# Open433_2020-06-20_13-22-58.net
KiCad netlist of a schematic drawn in EasyEDA
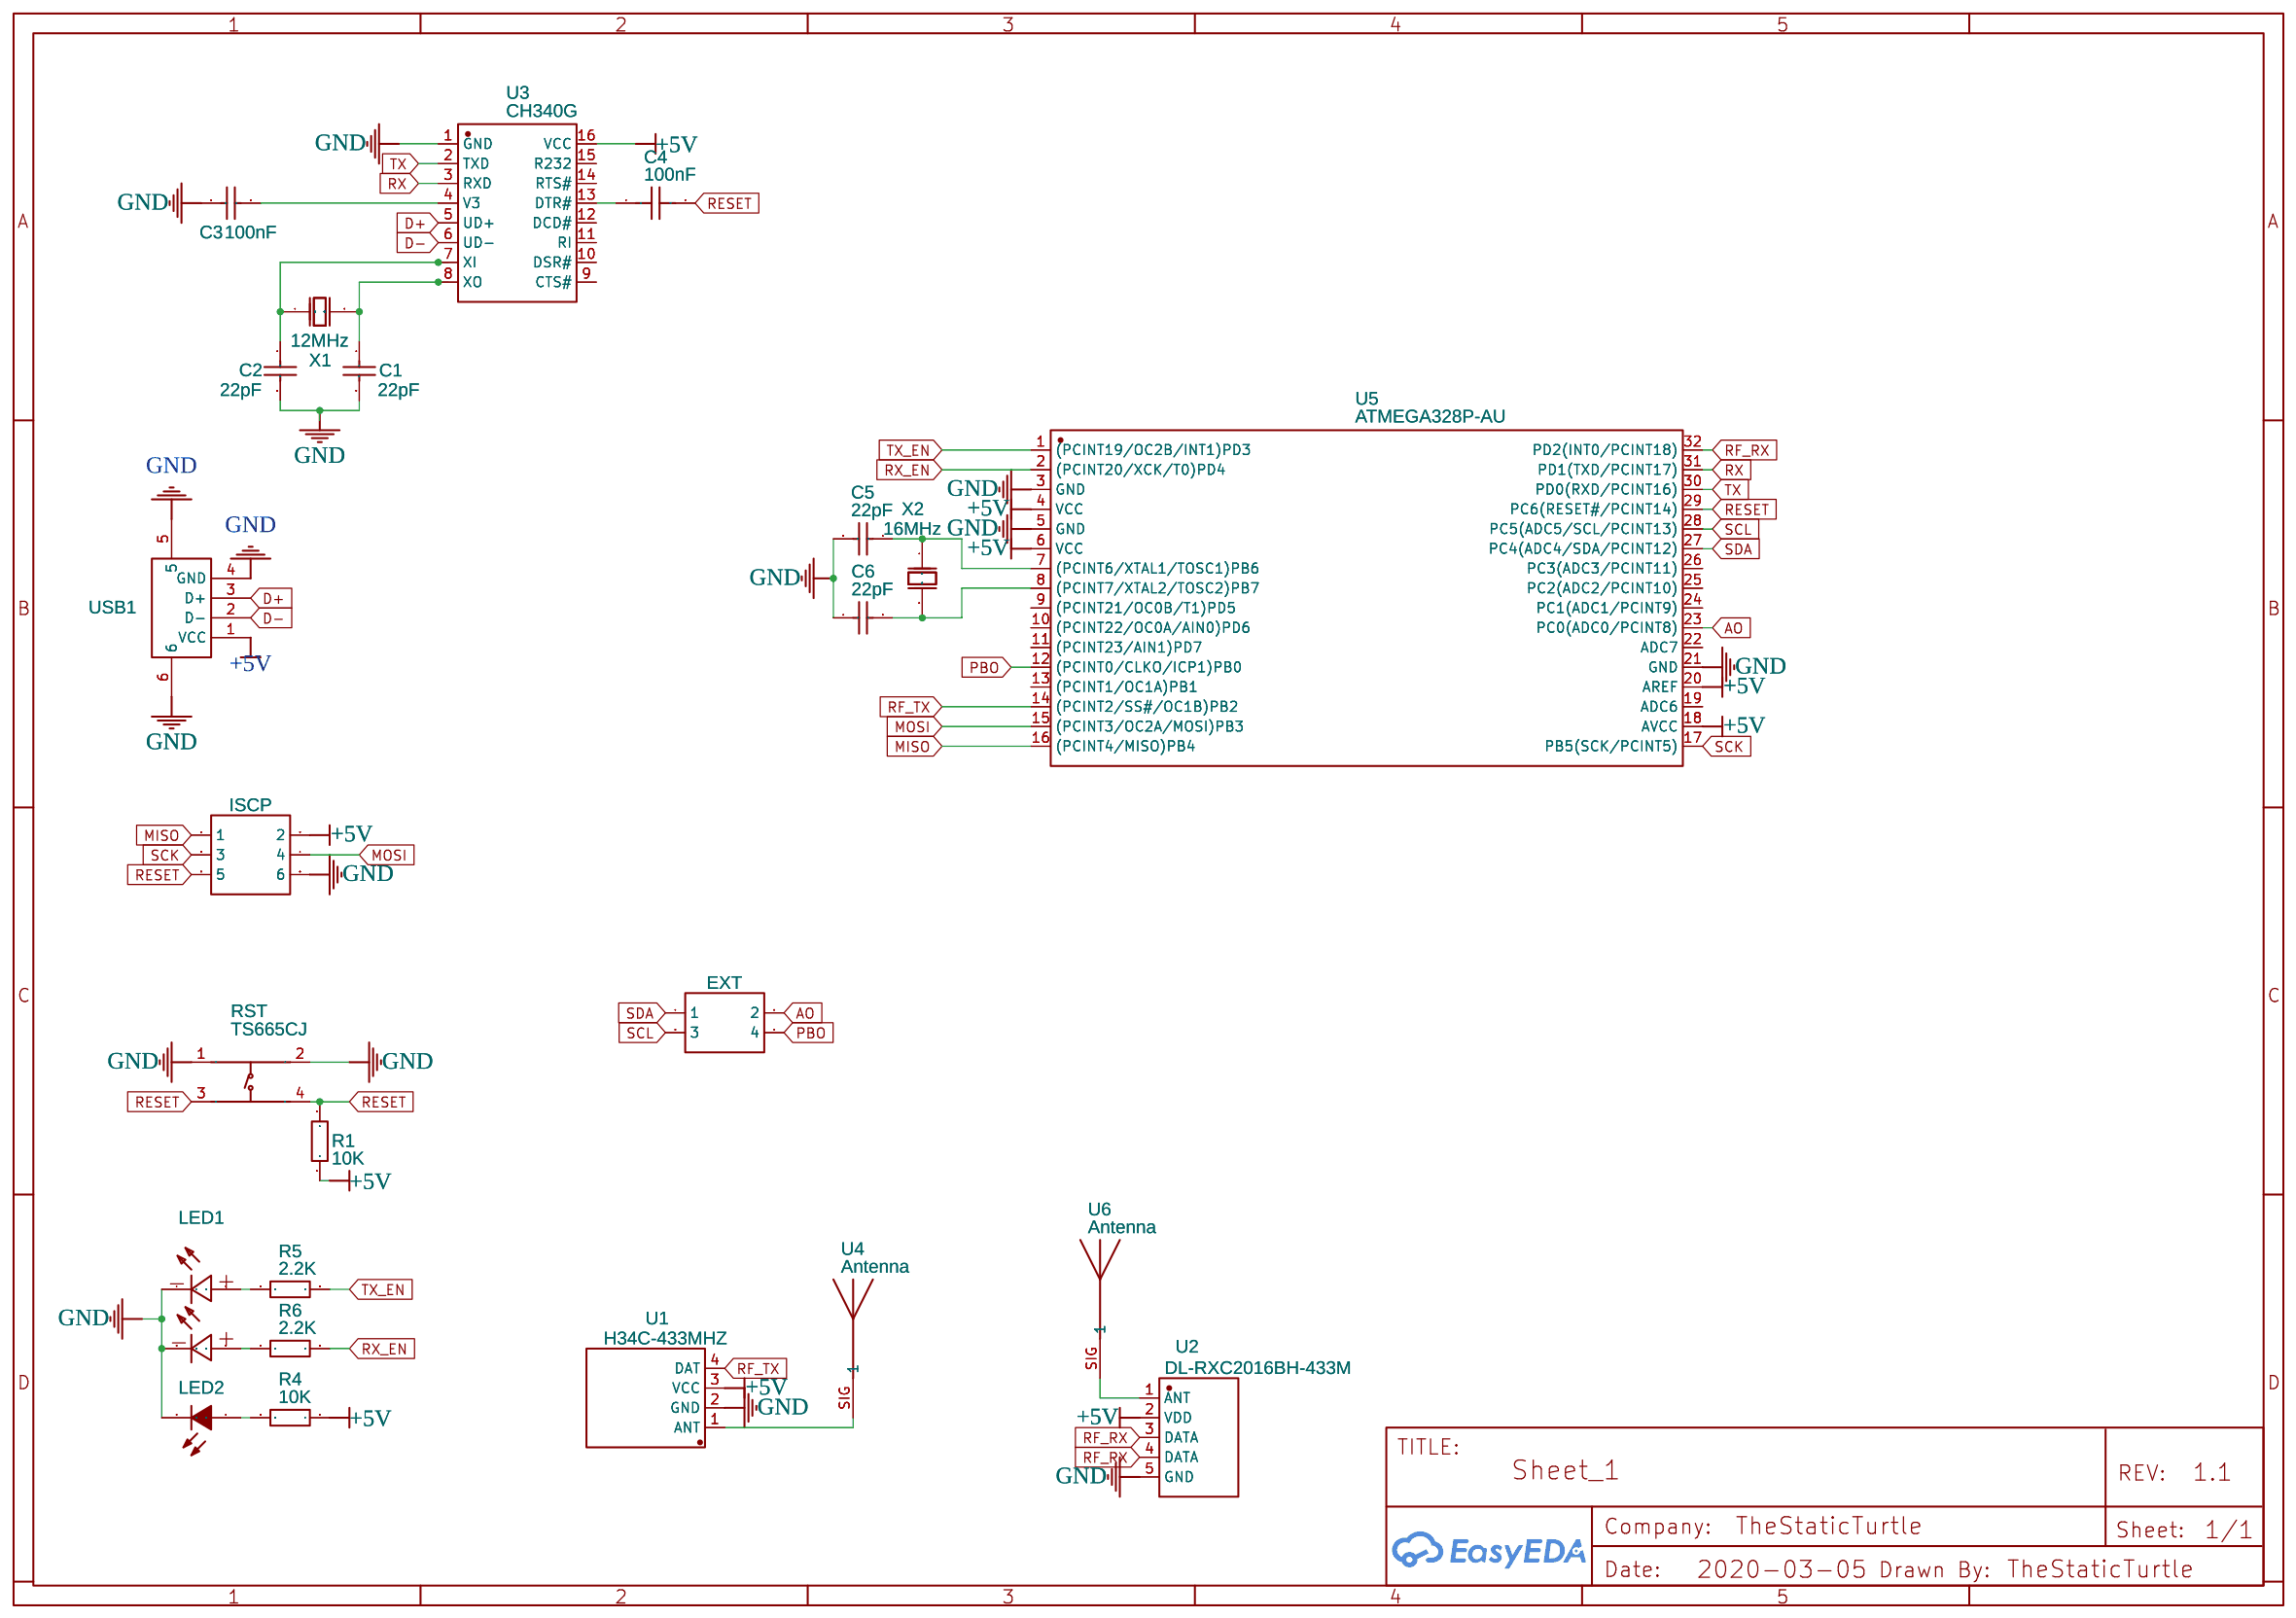
[diagram p0: schematic sheet]

(export (version "E")
  (design (tool "Eeschema 10.0.6"))
  (components
    (comp (ref "C1")
      (value "22pF")
      (fields
        (field (name "BOM_Manufacturer Part") "1206CG220J500NT")
        (field (name "BOM_Supplier Part") "C1896")
      )
      (libsource (lib "") (part "1206CG220J500NT_1"))
    )
    (comp (ref "C2")
      (value "22pF")
      (fields
        (field (name "BOM_Manufacturer Part") "1206CG220J500NT")
        (field (name "BOM_Supplier Part") "C1896")
      )
      (libsource (lib "") (part "1206CG220J500NT_1"))
    )
    (comp (ref "C3")
      (value "100nF")
      (fields
        (field (name "BOM_Manufacturer Part") "GRM31C5C1H104JA01L")
        (field (name "BOM_Supplier Part") "C97946")
      )
      (libsource (lib "") (part "GRM31C5C1H104JA01L"))
    )
    (comp (ref "C4")
      (value "100nF")
      (fields
        (field (name "BOM_Manufacturer Part") "FM31X104K251EEG")
        (field (name "BOM_Supplier Part") "C365814")
      )
      (libsource (lib "") (part "FM31X104K251EEG"))
    )
    (comp (ref "C5")
      (value "22pF")
      (fields
        (field (name "BOM_Manufacturer Part") "1206CG220J500NT")
        (field (name "BOM_Supplier Part") "C1896")
      )
      (libsource (lib "") (part "1206CG220J500NT"))
    )
    (comp (ref "C6")
      (value "22pF")
      (fields
        (field (name "BOM_Manufacturer Part") "1206CG220J500NT")
        (field (name "BOM_Supplier Part") "C1896")
      )
      (libsource (lib "") (part "1206CG220J500NT_2"))
    )
    (comp (ref "EXT")
      (value "HDR-M-2.54_2x2")
      (fields (field (name "BOM_Supplier Part") "C66690"))
      (libsource (lib "") (part "HDR-M-2.54_2x2"))
    )
    (comp (ref "ISCP")
      (value "Header-Female-2.54_2x3")
      (fields
        (field (name "BOM_Manufacturer Part") "DS1023-2*3SF11")
        (field (name "BOM_Supplier Part") "C92272")
      )
      (libsource (lib "") (part "Header-Female-2.54_2x3"))
    )
    (comp (ref "LED1")
      (value "19-223/Y2R6C-A01/2T")
      (fields (field (name "BOM_Supplier Part") "C282134"))
      (libsource (lib "") (part "19-223/Y2R6C-A01/2T"))
    )
    (comp (ref "LED2")
      (value "19-217/GHC-YR1S2/3T")
      (fields (field (name "BOM_Supplier Part") "C72043"))
      (libsource (lib "") (part "19-217/GHC-YR1S2/3T"))
    )
    (comp (ref "R1")
      (value "10K")
      (fields
        (field (name "BOM_Manufacturer Part") "CR-06JL7---10K")
        (field (name "BOM_Supplier Part") "C280032")
      )
      (libsource (lib "") (part "CR-06JL7---10K"))
    )
    (comp (ref "R4")
      (value "10K")
      (fields
        (field (name "BOM_Manufacturer Part") "CR-06JL7---10K")
        (field (name "BOM_Supplier Part") "C280032")
      )
      (libsource (lib "") (part "CR-06JL7---10K_1"))
    )
    (comp (ref "R5")
      (value "2.2K")
      (fields
        (field (name "BOM_Manufacturer Part") "QR0603F2K2P05")
        (field (name "BOM_Supplier Part") "C176136")
      )
      (libsource (lib "") (part "QR0603F2K2P05"))
    )
    (comp (ref "R6")
      (value "2.2K")
      (fields
        (field (name "BOM_Manufacturer Part") "QR0603F2K2P05")
        (field (name "BOM_Supplier Part") "C176136")
      )
      (libsource (lib "") (part "QR0603F2K2P05"))
    )
    (comp (ref "RST")
      (value "TS665CJ")
      (fields (field (name "BOM_Supplier Part") "C393938"))
      (libsource (lib "") (part "TS665CJ"))
    )
    (comp (ref "U1")
      (value "H34C-433MHZ")
      (fields (field (name "BOM_Supplier Part") "C131030"))
      (libsource (lib "") (part "H34C-433MHZ"))
    )
    (comp (ref "U2")
      (value "DL-RXC2016BH-433M")
      (fields (field (name "BOM_Supplier Part") "C381154"))
      (libsource (lib "") (part "DL-RXC2016BH-433M"))
    )
    (comp (ref "U3")
      (value "CH340G")
      (fields (field (name "BOM_Supplier Part") "C14267"))
      (libsource (lib "") (part "CH340G"))
    )
    (comp (ref "U4")
      (value "Antenna")
      (fields (field (name "BOM_Manufacturer Part") "ANT"))
      (libsource (lib "") (part "Antenna"))
    )
    (comp (ref "U5")
      (value "ATMEGA328P-AU")
      (fields (field (name "BOM_Supplier Part") "C14877"))
      (libsource (lib "") (part "ATMEGA328P-AU"))
    )
    (comp (ref "U6")
      (value "Antenna")
      (fields (field (name "BOM_Manufacturer Part") "ANT"))
      (libsource (lib "") (part "Antenna"))
    )
    (comp (ref "USB1")
      (value "U217-04XN-XXR84")
      (fields (field (name "BOM_Supplier Part") "C319178"))
      (libsource (lib "") (part "U217-04XN-XXR84"))
    )
    (comp (ref "X1")
      (value "12MHz")
      (fields
        (field (name "BOM_Manufacturer Part") "C12000J517")
        (field (name "BOM_Supplier Part") "C279578")
      )
      (libsource (lib "") (part "C12000J517"))
    )
    (comp (ref "X2")
      (value "16MHz")
      (fields
        (field (name "BOM_Manufacturer Part") "49MD-16.000-20-20-20/A")
        (field (name "BOM_Supplier Part") "C240963")
      )
      (libsource (lib "") (part "49MD-16.000-20-20-20/A"))
    )
  )
  (nets
    (net (code "1") (name "+5V") (class "Default")
      (node (ref "ISCP") (pin "2") (pinfunction "2_2") (pintype "input"))
      (node (ref "R1") (pin "1") (pinfunction "1_1") (pintype "unspecified"))
      (node (ref "R4") (pin "1") (pinfunction "1_1") (pintype "unspecified"))
      (node (ref "U1") (pin "3") (pinfunction "VCC_3") (pintype "unspecified"))
      (node (ref "U2") (pin "2") (pinfunction "VDD_2") (pintype "unspecified"))
      (node (ref "U3") (pin "16") (pinfunction "VCC_16") (pintype "unspecified"))
      (node (ref "U5") (pin "18") (pinfunction "AVCC_18") (pintype "unspecified"))
      (node (ref "U5") (pin "20") (pinfunction "AREF_20") (pintype "unspecified"))
      (node (ref "U5") (pin "4") (pinfunction "VCC_4") (pintype "unspecified"))
      (node (ref "U5") (pin "6") (pinfunction "VCC_6") (pintype "unspecified"))
      (node (ref "USB1") (pin "1") (pinfunction "VCC_1") (pintype "unspecified"))
    )
    (net (code "2") (name "AO") (class "Default")
      (node (ref "EXT") (pin "2") (pinfunction "2_2") (pintype "input"))
      (node (ref "U5") (pin "23") (pinfunction "PC0(ADC0/PCINT8)_23") (pintype "unspecified"))
    )
    (net (code "3") (name "D+") (class "Default")
      (node (ref "U3") (pin "5") (pinfunction "UD+_5") (pintype "unspecified"))
      (node (ref "USB1") (pin "3") (pinfunction "D+_3") (pintype "unspecified"))
    )
    (net (code "4") (name "D-") (class "Default")
      (node (ref "U3") (pin "6") (pinfunction "UD-_6") (pintype "unspecified"))
      (node (ref "USB1") (pin "2") (pinfunction "D-_2") (pintype "unspecified"))
    )
    (net (code "5") (name "GND") (class "Default")
      (node (ref "C1") (pin "2") (pinfunction "2_2") (pintype "input"))
      (node (ref "C2") (pin "2") (pinfunction "2_2") (pintype "input"))
      (node (ref "C3") (pin "1") (pinfunction "1_1") (pintype "input"))
      (node (ref "C5") (pin "2") (pinfunction "2_2") (pintype "input"))
      (node (ref "C6") (pin "1") (pinfunction "1_1") (pintype "input"))
      (node (ref "ISCP") (pin "6") (pinfunction "6_6") (pintype "input"))
      (node (ref "LED1") (pin "3") (pinfunction "3_3") (pintype "unspecified"))
      (node (ref "LED1") (pin "4") (pinfunction "4_4") (pintype "unspecified"))
      (node (ref "LED2") (pin "2") (pinfunction "C_2") (pintype "input"))
      (node (ref "RST") (pin "1") (pinfunction "A_1") (pintype "unspecified"))
      (node (ref "RST") (pin "2") (pinfunction "B_2") (pintype "unspecified"))
      (node (ref "U1") (pin "2") (pinfunction "GND_2") (pintype "unspecified"))
      (node (ref "U2") (pin "5") (pinfunction "GND_5") (pintype "unspecified"))
      (node (ref "U3") (pin "1") (pinfunction "GND_1") (pintype "unspecified"))
      (node (ref "U5") (pin "21") (pinfunction "GND_21") (pintype "unspecified"))
      (node (ref "U5") (pin "3") (pinfunction "GND_3") (pintype "unspecified"))
      (node (ref "U5") (pin "5") (pinfunction "GND_5") (pintype "unspecified"))
      (node (ref "USB1") (pin "4") (pinfunction "GND_4") (pintype "unspecified"))
      (node (ref "USB1") (pin "5") (pinfunction "5_5") (pintype "unspecified"))
      (node (ref "USB1") (pin "6") (pinfunction "6_6") (pintype "unspecified"))
    )
    (net (code "6") (name "MISO") (class "Default")
      (node (ref "ISCP") (pin "1") (pinfunction "1_1") (pintype "input"))
      (node (ref "U5") (pin "16") (pinfunction "(PCINT4/MISO)PB4_16") (pintype "unspecified"))
    )
    (net (code "7") (name "MOSI") (class "Default")
      (node (ref "ISCP") (pin "4") (pinfunction "4_4") (pintype "input"))
      (node (ref "U5") (pin "15") (pinfunction "(PCINT3/OC2A/MOSI)PB3_15") (pintype "unspecified"))
    )
    (net (code "8") (name "Net-(LED1-Pad1)") (class "Default")
      (node (ref "LED1") (pin "1") (pinfunction "1_1") (pintype "unspecified"))
      (node (ref "R5") (pin "1") (pinfunction "1_1") (pintype "unspecified"))
    )
    (net (code "9") (name "Net-(LED1-Pad2)") (class "Default")
      (node (ref "LED1") (pin "2") (pinfunction "2_2") (pintype "unspecified"))
      (node (ref "R6") (pin "1") (pinfunction "1_1") (pintype "unspecified"))
    )
    (net (code "10") (name "Net-(LED2-A)") (class "Default")
      (node (ref "LED2") (pin "1") (pinfunction "A_1") (pintype "input"))
      (node (ref "R4") (pin "2") (pinfunction "2_2") (pintype "unspecified"))
    )
    (net (code "11") (name "Net-(U1-ANT)") (class "Default")
      (node (ref "U1") (pin "1") (pinfunction "ANT_1") (pintype "unspecified"))
      (node (ref "U4") (pin "SIG") (pinfunction "1_SIG") (pintype "unspecified"))
    )
    (net (code "12") (name "Net-(U2-ANT)") (class "Default")
      (node (ref "U2") (pin "1") (pinfunction "ANT_1") (pintype "unspecified"))
      (node (ref "U6") (pin "SIG") (pinfunction "1_SIG") (pintype "unspecified"))
    )
    (net (code "13") (name "Net-(U3-DTR#)") (class "Default")
      (node (ref "C4") (pin "1") (pinfunction "1_1") (pintype "unspecified"))
      (node (ref "U3") (pin "13") (pinfunction "DTR#_13") (pintype "unspecified"))
    )
    (net (code "14") (name "Net-(U3-V3)") (class "Default")
      (node (ref "C3") (pin "2") (pinfunction "2_2") (pintype "input"))
      (node (ref "U3") (pin "4") (pinfunction "V3_4") (pintype "unspecified"))
    )
    (net (code "15") (name "Net-(U3-XI)") (class "Default")
      (node (ref "C2") (pin "1") (pinfunction "1_1") (pintype "input"))
      (node (ref "U3") (pin "7") (pinfunction "XI_7") (pintype "unspecified"))
      (node (ref "X1") (pin "1") (pinfunction "OSC1_1") (pintype "input"))
    )
    (net (code "16") (name "Net-(U3-XO)") (class "Default")
      (node (ref "C1") (pin "1") (pinfunction "1_1") (pintype "input"))
      (node (ref "U3") (pin "8") (pinfunction "XO_8") (pintype "unspecified"))
      (node (ref "X1") (pin "2") (pinfunction "OSC2_2") (pintype "input"))
    )
    (net (code "17") (name "Net-(U5-(PCINT6{slash}XTAL1{slash}TOSC1)PB6)") (class "Default")
      (node (ref "C5") (pin "1") (pinfunction "1_1") (pintype "input"))
      (node (ref "U5") (pin "7") (pinfunction "(PCINT6/XTAL1/TOSC1)PB6_7") (pintype "unspecified"))
      (node (ref "X2") (pin "1") (pinfunction "OSC1_1") (pintype "input"))
    )
    (net (code "18") (name "Net-(U5-(PCINT7{slash}XTAL2{slash}TOSC2)PB7)") (class "Default")
      (node (ref "C6") (pin "2") (pinfunction "2_2") (pintype "input"))
      (node (ref "U5") (pin "8") (pinfunction "(PCINT7/XTAL2/TOSC2)PB7_8") (pintype "unspecified"))
      (node (ref "X2") (pin "2") (pinfunction "OSC2_2") (pintype "input"))
    )
    (net (code "19") (name "PBO") (class "Default")
      (node (ref "EXT") (pin "4") (pinfunction "4_4") (pintype "input"))
      (node (ref "U5") (pin "12") (pinfunction "(PCINT0/CLKO/ICP1)PB0_12") (pintype "unspecified"))
    )
    (net (code "20") (name "RESET") (class "Default")
      (node (ref "C4") (pin "2") (pinfunction "2_2") (pintype "unspecified"))
      (node (ref "ISCP") (pin "5") (pinfunction "5_5") (pintype "input"))
      (node (ref "R1") (pin "2") (pinfunction "2_2") (pintype "unspecified"))
      (node (ref "RST") (pin "3") (pinfunction "C_3") (pintype "unspecified"))
      (node (ref "RST") (pin "4") (pinfunction "D_4") (pintype "unspecified"))
      (node (ref "U5") (pin "29") (pinfunction "PC6(RESET#/PCINT14)_29") (pintype "unspecified"))
    )
    (net (code "21") (name "RF_RX") (class "Default")
      (node (ref "U2") (pin "3") (pinfunction "DATA_3") (pintype "unspecified"))
      (node (ref "U2") (pin "4") (pinfunction "DATA_4") (pintype "unspecified"))
      (node (ref "U5") (pin "32") (pinfunction "PD2(INT0/PCINT18)_32") (pintype "unspecified"))
    )
    (net (code "22") (name "RF_TX") (class "Default")
      (node (ref "U1") (pin "4") (pinfunction "DAT_4") (pintype "unspecified"))
      (node (ref "U5") (pin "14") (pinfunction "(PCINT2/SS#/OC1B)PB2_14") (pintype "unspecified"))
    )
    (net (code "23") (name "RX") (class "Default")
      (node (ref "U3") (pin "3") (pinfunction "RXD_3") (pintype "unspecified"))
      (node (ref "U5") (pin "31") (pinfunction "PD1(TXD/PCINT17)_31") (pintype "unspecified"))
    )
    (net (code "24") (name "RX_EN") (class "Default")
      (node (ref "R6") (pin "2") (pinfunction "2_2") (pintype "unspecified"))
      (node (ref "U5") (pin "2") (pinfunction "(PCINT20/XCK/T0)PD4_2") (pintype "unspecified"))
    )
    (net (code "25") (name "SCK") (class "Default")
      (node (ref "ISCP") (pin "3") (pinfunction "3_3") (pintype "input"))
      (node (ref "U5") (pin "17") (pinfunction "PB5(SCK/PCINT5)_17") (pintype "unspecified"))
    )
    (net (code "26") (name "SCL") (class "Default")
      (node (ref "EXT") (pin "3") (pinfunction "3_3") (pintype "input"))
      (node (ref "U5") (pin "28") (pinfunction "PC5(ADC5/SCL/PCINT13)_28") (pintype "unspecified"))
    )
    (net (code "27") (name "SDA") (class "Default")
      (node (ref "EXT") (pin "1") (pinfunction "1_1") (pintype "input"))
      (node (ref "U5") (pin "27") (pinfunction "PC4(ADC4/SDA/PCINT12)_27") (pintype "unspecified"))
    )
    (net (code "28") (name "TX") (class "Default")
      (node (ref "U3") (pin "2") (pinfunction "TXD_2") (pintype "unspecified"))
      (node (ref "U5") (pin "30") (pinfunction "PD0(RXD/PCINT16)_30") (pintype "unspecified"))
    )
    (net (code "29") (name "TX_EN") (class "Default")
      (node (ref "R5") (pin "2") (pinfunction "2_2") (pintype "unspecified"))
      (node (ref "U5") (pin "1") (pinfunction "(PCINT19/OC2B/INT1)PD3_1") (pintype "unspecified"))
    )
    (net (code "30") (name "unconnected-(U3-CTS#-Pad9)") (class "Default")
      (node (ref "U3") (pin "9") (pinfunction "CTS#_9") (pintype "unspecified"))
    )
    (net (code "31") (name "unconnected-(U3-DCD#-Pad12)") (class "Default")
      (node (ref "U3") (pin "12") (pinfunction "DCD#_12") (pintype "unspecified"))
    )
    (net (code "32") (name "unconnected-(U3-DSR#-Pad10)") (class "Default")
      (node (ref "U3") (pin "10") (pinfunction "DSR#_10") (pintype "unspecified"))
    )
    (net (code "33") (name "unconnected-(U3-R232-Pad15)") (class "Default")
      (node (ref "U3") (pin "15") (pinfunction "R232_15") (pintype "unspecified"))
    )
    (net (code "34") (name "unconnected-(U3-RI-Pad11)") (class "Default")
      (node (ref "U3") (pin "11") (pinfunction "RI_11") (pintype "unspecified"))
    )
    (net (code "35") (name "unconnected-(U3-RTS#-Pad14)") (class "Default")
      (node (ref "U3") (pin "14") (pinfunction "RTS#_14") (pintype "unspecified"))
    )
    (net (code "36") (name "unconnected-(U5-(PCINT1{slash}OC1A)PB1-Pad13)") (class "Default")
      (node (ref "U5") (pin "13") (pinfunction "(PCINT1/OC1A)PB1_13") (pintype "unspecified"))
    )
    (net (code "37") (name "unconnected-(U5-(PCINT21{slash}OC0B{slash}T1)PD5-Pad9)") (class "Default")
      (node (ref "U5") (pin "9") (pinfunction "(PCINT21/OC0B/T1)PD5_9") (pintype "unspecified"))
    )
    (net (code "38") (name "unconnected-(U5-(PCINT22{slash}OC0A{slash}AIN0)PD6-Pad10)") (class "Default")
      (node (ref "U5") (pin "10") (pinfunction "(PCINT22/OC0A/AIN0)PD6_10") (pintype "unspecified"))
    )
    (net (code "39") (name "unconnected-(U5-(PCINT23{slash}AIN1)PD7-Pad11)") (class "Default")
      (node (ref "U5") (pin "11") (pinfunction "(PCINT23/AIN1)PD7_11") (pintype "unspecified"))
    )
    (net (code "40") (name "unconnected-(U5-ADC6-Pad19)") (class "Default")
      (node (ref "U5") (pin "19") (pinfunction "ADC6_19") (pintype "unspecified"))
    )
    (net (code "41") (name "unconnected-(U5-ADC7-Pad22)") (class "Default")
      (node (ref "U5") (pin "22") (pinfunction "ADC7_22") (pintype "unspecified"))
    )
    (net (code "42") (name "unconnected-(U5-PC1(ADC1{slash}PCINT9)-Pad24)") (class "Default")
      (node (ref "U5") (pin "24") (pinfunction "PC1(ADC1/PCINT9)_24") (pintype "unspecified"))
    )
    (net (code "43") (name "unconnected-(U5-PC2(ADC2{slash}PCINT10)-Pad25)") (class "Default")
      (node (ref "U5") (pin "25") (pinfunction "PC2(ADC2/PCINT10)_25") (pintype "unspecified"))
    )
    (net (code "44") (name "unconnected-(U5-PC3(ADC3{slash}PCINT11)-Pad26)") (class "Default")
      (node (ref "U5") (pin "26") (pinfunction "PC3(ADC3/PCINT11)_26") (pintype "unspecified"))
    )
  )
)
